# Wifi-Bluetooth-Power.net
KiCad netlist of a schematic drawn in Altium Designer
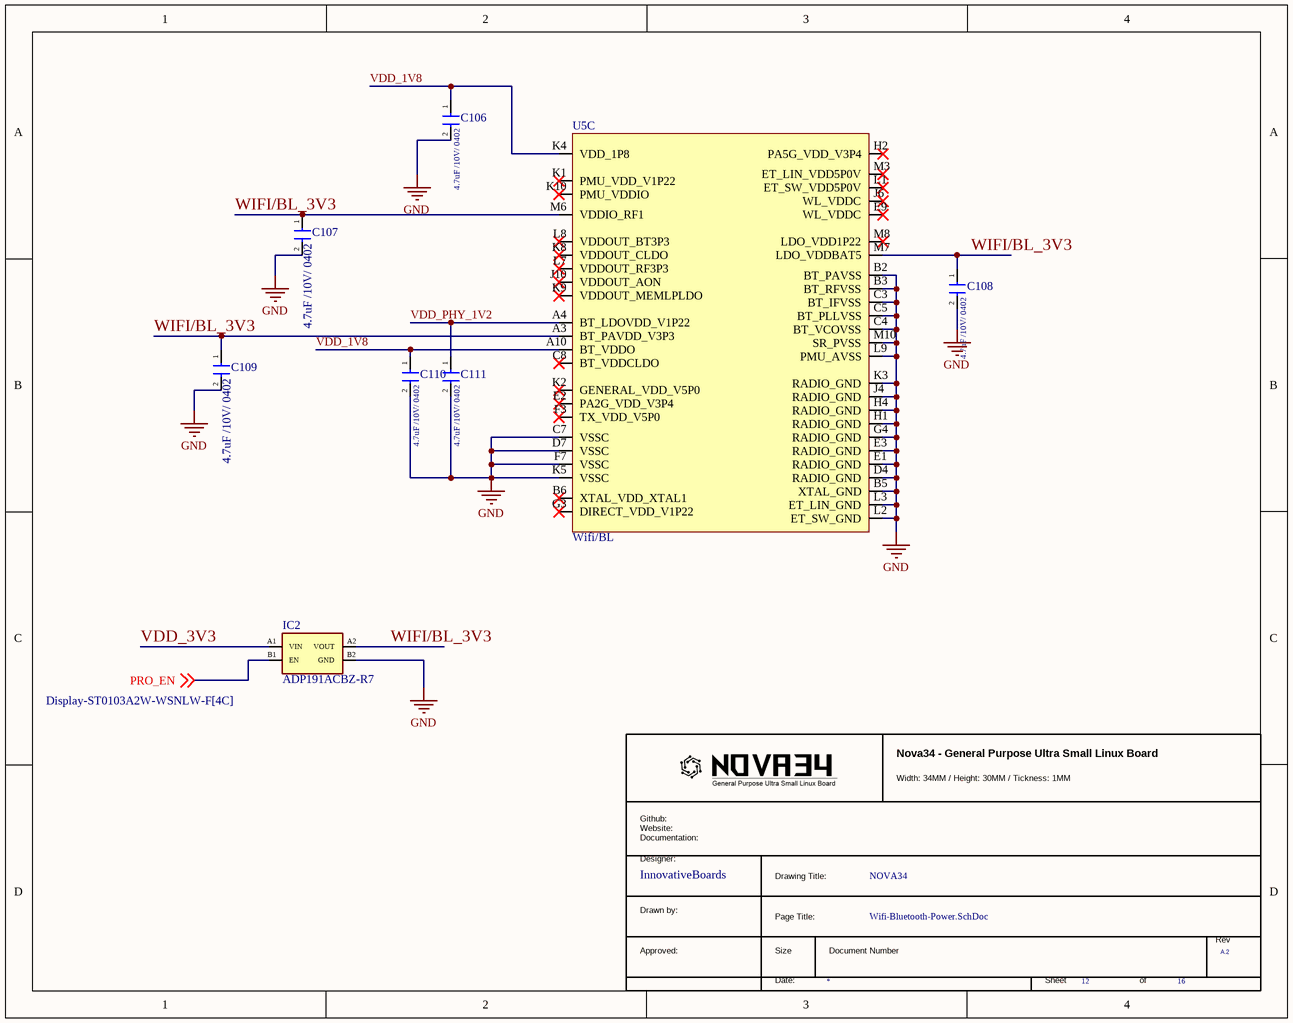
[diagram p0: Wifi-Bluetooth-Power.SchDoc]

(export (version "E")
  (design (tool "Eeschema 10.0.6"))
  (components
    (comp (ref "*")
      (value "TitleBlock_MCPG")
      (fields (field (name "REVCODE") "A.2"))
      (libsource (lib "Nova_SCHLIB") (part "TitleBlock_MCPG"))
    )
    (comp (ref "C106")
      (value "4.7uF /10V/ 0402")
      (footprint "CAPC1005X70N")
      (description "Multilayer Ceramic Capacitors MLCC - SMD/SMT 0402 X6S 4.7 F 20 10VDC AEC-Q200")
      (fields
        (field (name "MANUFACTURER_PART_NUMBER") "GRT155C81A475ME13J")
        (field (name "MOUSER PART NUMBER") "81-GRT155C81A475ME3J")
      )
      (libsource (lib "Nova_SCHLIB") (part "GRT155C81A475ME13J"))
    )
    (comp (ref "C107")
      (value "4.7uF /10V/ 0402")
      (footprint "CAPC1005X70N")
      (description "Multilayer Ceramic Capacitors MLCC - SMD/SMT 0402 X6S 4.7 F 20 10VDC AEC-Q200")
      (fields
        (field (name "MANUFACTURER_PART_NUMBER") "GRT155C81A475ME13J")
        (field (name "MOUSER PART NUMBER") "81-GRT155C81A475ME3J")
      )
      (libsource (lib "Nova_SCHLIB") (part "GRT155C81A475ME13J"))
    )
    (comp (ref "C108")
      (value "4.7uF /10V/ 0402")
      (footprint "CAPC1005X70N")
      (description "Multilayer Ceramic Capacitors MLCC - SMD/SMT 0402 X6S 4.7 F 20 10VDC AEC-Q200")
      (fields
        (field (name "MANUFACTURER_PART_NUMBER") "GRT155C81A475ME13J")
        (field (name "MOUSER PART NUMBER") "81-GRT155C81A475ME3J")
      )
      (libsource (lib "Nova_SCHLIB") (part "GRT155C81A475ME13J"))
    )
    (comp (ref "C109")
      (value "4.7uF /10V/ 0402")
      (footprint "CAPC1005X70N")
      (description "Multilayer Ceramic Capacitors MLCC - SMD/SMT 0402 X6S 4.7 F 20 10VDC AEC-Q200")
      (fields
        (field (name "MANUFACTURER_PART_NUMBER") "GRT155C81A475ME13J")
        (field (name "MOUSER PART NUMBER") "81-GRT155C81A475ME3J")
      )
      (libsource (lib "Nova_SCHLIB") (part "GRT155C81A475ME13J"))
    )
    (comp (ref "C110")
      (value "4.7uF /10V/ 0402")
      (footprint "CAPC1005X70N")
      (description "Multilayer Ceramic Capacitors MLCC - SMD/SMT 0402 X6S 4.7 F 20 10VDC AEC-Q200")
      (fields
        (field (name "MANUFACTURER_PART_NUMBER") "GRT155C81A475ME13J")
        (field (name "MOUSER PART NUMBER") "81-GRT155C81A475ME3J")
      )
      (libsource (lib "Nova_SCHLIB") (part "GRT155C81A475ME13J"))
    )
    (comp (ref "C111")
      (value "4.7uF /10V/ 0402")
      (footprint "CAPC1005X70N")
      (description "Multilayer Ceramic Capacitors MLCC - SMD/SMT 0402 X6S 4.7 F 20 10VDC AEC-Q200")
      (fields
        (field (name "MANUFACTURER_PART_NUMBER") "GRT155C81A475ME13J")
        (field (name "MOUSER PART NUMBER") "81-GRT155C81A475ME3J")
      )
      (libsource (lib "Nova_SCHLIB") (part "GRT155C81A475ME13J"))
    )
    (comp (ref "IC2")
      (value "ADP191ACBZ-R7")
      (footprint "BGA4C40P2X2_76X76X66")
      (description "Integrated Circuit")
      (fields (field (name "MOUSER PART NUMBER") "584-ADP191ACBZ-R7"))
      (libsource (lib "Nova_SCHLIB") (part "ADP191ACBZ-R7"))
    )
    (comp (ref "U5")
      (value "Wifi/BL")
      (footprint "106 BALL WLBGA 3.76X4.43X0.53 MM")
      (libsource (lib "Nova_SCHLIB") (part "CYW43012"))
    )
  )
  (nets
    (net (code "1") (name "/VDD_1V8") (class "Default")
      (node (ref "C106") (pin "1") (pinfunction "1_1") (pintype "passive"))
      (node (ref "C110") (pin "1") (pinfunction "1_1") (pintype "passive"))
      (node (ref "U5") (pin "A10") (pinfunction "BT_VDDO_A10") (pintype "passive"))
      (node (ref "U5") (pin "K4") (pinfunction "VDD_1P8_K4") (pintype "passive"))
    )
    (net (code "2") (name "/VDD_3V3") (class "Default")
      (node (ref "IC2") (pin "A1") (pinfunction "VIN_A1") (pintype "passive"))
    )
    (net (code "3") (name "/VDD_PHY_1V2") (class "Default")
      (node (ref "C111") (pin "1") (pinfunction "1_1") (pintype "passive"))
      (node (ref "U5") (pin "A4") (pinfunction "BT_LDOVDD_V1P22_A4") (pintype "passive"))
    )
    (net (code "4") (name "/WIFI{slash}BL_3V3") (class "Default")
      (node (ref "C107") (pin "1") (pinfunction "1_1") (pintype "passive"))
      (node (ref "C108") (pin "1") (pinfunction "1_1") (pintype "passive"))
      (node (ref "C109") (pin "1") (pinfunction "1_1") (pintype "passive"))
      (node (ref "IC2") (pin "A2") (pinfunction "VOUT_A2") (pintype "passive"))
      (node (ref "U5") (pin "A3") (pinfunction "BT_PAVDD_V3P3_A3") (pintype "passive"))
      (node (ref "U5") (pin "M6") (pinfunction "VDDIO_RF1_M6") (pintype "passive"))
      (node (ref "U5") (pin "M7") (pinfunction "LDO_VDDBAT5_M7") (pintype "passive"))
    )
    (net (code "5") (name "GND") (class "Default")
      (node (ref "C106") (pin "2") (pinfunction "2_2") (pintype "passive"))
      (node (ref "C107") (pin "2") (pinfunction "2_2") (pintype "passive"))
      (node (ref "C108") (pin "2") (pinfunction "2_2") (pintype "passive"))
      (node (ref "C109") (pin "2") (pinfunction "2_2") (pintype "passive"))
      (node (ref "C110") (pin "2") (pinfunction "2_2") (pintype "passive"))
      (node (ref "C111") (pin "2") (pinfunction "2_2") (pintype "passive"))
      (node (ref "IC2") (pin "B2") (pinfunction "GND_B2") (pintype "passive"))
      (node (ref "U5") (pin "B2") (pinfunction "BT_PAVSS_B2") (pintype "passive"))
      (node (ref "U5") (pin "B3") (pinfunction "BT_RFVSS_B3") (pintype "passive"))
      (node (ref "U5") (pin "B5") (pinfunction "XTAL_GND_B5") (pintype "passive"))
      (node (ref "U5") (pin "C3") (pinfunction "BT_IFVSS_C3") (pintype "passive"))
      (node (ref "U5") (pin "C4") (pinfunction "BT_VCOVSS_C4") (pintype "passive"))
      (node (ref "U5") (pin "C5") (pinfunction "BT_PLLVSS_C5") (pintype "passive"))
      (node (ref "U5") (pin "C7") (pinfunction "VSSC_C7") (pintype "passive"))
      (node (ref "U5") (pin "D4") (pinfunction "RADIO_GND_D4") (pintype "passive"))
      (node (ref "U5") (pin "D7") (pinfunction "VSSC_D7") (pintype "passive"))
      (node (ref "U5") (pin "E1") (pinfunction "RADIO_GND_E1") (pintype "passive"))
      (node (ref "U5") (pin "E3") (pinfunction "RADIO_GND_E3") (pintype "passive"))
      (node (ref "U5") (pin "F7") (pinfunction "VSSC_F7") (pintype "passive"))
      (node (ref "U5") (pin "G4") (pinfunction "RADIO_GND_G4") (pintype "passive"))
      (node (ref "U5") (pin "H1") (pinfunction "RADIO_GND_H1") (pintype "passive"))
      (node (ref "U5") (pin "H4") (pinfunction "RADIO_GND_H4") (pintype "passive"))
      (node (ref "U5") (pin "J4") (pinfunction "RADIO_GND_J4") (pintype "passive"))
      (node (ref "U5") (pin "K3") (pinfunction "RADIO_GND_K3") (pintype "passive"))
      (node (ref "U5") (pin "K5") (pinfunction "VSSC_K5") (pintype "passive"))
      (node (ref "U5") (pin "L2") (pinfunction "ET_SW_GND_L2") (pintype "passive"))
      (node (ref "U5") (pin "L3") (pinfunction "ET_LIN_GND_L3") (pintype "passive"))
      (node (ref "U5") (pin "L9") (pinfunction "PMU_AVSS_L9") (pintype "passive"))
      (node (ref "U5") (pin "M10") (pinfunction "SR_PVSS_M10") (pintype "passive"))
    )
    (net (code "6") (name "PRO_EN") (class "Default")
      (node (ref "IC2") (pin "B1") (pinfunction "EN_B1") (pintype "passive"))
    )
    (net (code "7") (name "unconnected-(U5C-BT_VDDCLDO-PadC8)") (class "Default")
      (node (ref "U5") (pin "C8") (pinfunction "BT_VDDCLDO_C8") (pintype "passive+no_connect"))
    )
    (net (code "8") (name "unconnected-(U5C-DIRECT_VDD_V1P22-PadG3)") (class "Default")
      (node (ref "U5") (pin "G3") (pinfunction "DIRECT_VDD_V1P22_G3") (pintype "passive+no_connect"))
    )
    (net (code "9") (name "unconnected-(U5C-ET_LIN_VDD5P0V-PadM3)") (class "Default")
      (node (ref "U5") (pin "M3") (pinfunction "ET_LIN_VDD5P0V_M3") (pintype "passive+no_connect"))
    )
    (net (code "10") (name "unconnected-(U5C-ET_SW_VDD5P0V-PadL1)") (class "Default")
      (node (ref "U5") (pin "L1") (pinfunction "ET_SW_VDD5P0V_L1") (pintype "passive+no_connect"))
    )
    (net (code "11") (name "unconnected-(U5C-GENERAL_VDD_V5P0-PadK2)") (class "Default")
      (node (ref "U5") (pin "K2") (pinfunction "GENERAL_VDD_V5P0_K2") (pintype "passive+no_connect"))
    )
    (net (code "12") (name "unconnected-(U5C-LDO_VDD1P22-PadM8)") (class "Default")
      (node (ref "U5") (pin "M8") (pinfunction "LDO_VDD1P22_M8") (pintype "passive+no_connect"))
    )
    (net (code "13") (name "unconnected-(U5C-PA2G_VDD_V3P4-PadE2)") (class "Default")
      (node (ref "U5") (pin "E2") (pinfunction "PA2G_VDD_V3P4_E2") (pintype "passive+no_connect"))
    )
    (net (code "14") (name "unconnected-(U5C-PA5G_VDD_V3P4-PadH2)") (class "Default")
      (node (ref "U5") (pin "H2") (pinfunction "PA5G_VDD_V3P4_H2") (pintype "passive+no_connect"))
    )
    (net (code "15") (name "unconnected-(U5C-PMU_VDDIO-PadK10)") (class "Default")
      (node (ref "U5") (pin "K10") (pinfunction "PMU_VDDIO_K10") (pintype "passive+no_connect"))
    )
    (net (code "16") (name "unconnected-(U5C-PMU_VDD_V1P22-PadK1)") (class "Default")
      (node (ref "U5") (pin "K1") (pinfunction "PMU_VDD_V1P22_K1") (pintype "passive+no_connect"))
    )
    (net (code "17") (name "unconnected-(U5C-TX_VDD_V5P0-PadF3)") (class "Default")
      (node (ref "U5") (pin "F3") (pinfunction "TX_VDD_V5P0_F3") (pintype "passive+no_connect"))
    )
    (net (code "18") (name "unconnected-(U5C-VDDOUT_AON-PadJ10)") (class "Default")
      (node (ref "U5") (pin "J10") (pinfunction "VDDOUT_AON_J10") (pintype "passive+no_connect"))
    )
    (net (code "19") (name "unconnected-(U5C-VDDOUT_BT3P3-PadL8)") (class "Default")
      (node (ref "U5") (pin "L8") (pinfunction "VDDOUT_BT3P3_L8") (pintype "passive+no_connect"))
    )
    (net (code "20") (name "unconnected-(U5C-VDDOUT_CLDO-PadK8)") (class "Default")
      (node (ref "U5") (pin "K8") (pinfunction "VDDOUT_CLDO_K8") (pintype "passive+no_connect"))
    )
    (net (code "21") (name "unconnected-(U5C-VDDOUT_MEMLPLDO-PadK9)") (class "Default")
      (node (ref "U5") (pin "K9") (pinfunction "VDDOUT_MEMLPLDO_K9") (pintype "passive+no_connect"))
    )
    (net (code "22") (name "unconnected-(U5C-VDDOUT_RF3P3-PadL7)") (class "Default")
      (node (ref "U5") (pin "L7") (pinfunction "VDDOUT_RF3P3_L7") (pintype "passive+no_connect"))
    )
    (net (code "23") (name "unconnected-(U5C-WL_VDDC-PadE9)") (class "Default")
      (node (ref "U5") (pin "E9") (pinfunction "WL_VDDC_E9") (pintype "passive+no_connect"))
    )
    (net (code "24") (name "unconnected-(U5C-WL_VDDC-PadJ6)") (class "Default")
      (node (ref "U5") (pin "J6") (pinfunction "WL_VDDC_J6") (pintype "passive+no_connect"))
    )
    (net (code "25") (name "unconnected-(U5C-XTAL_VDD_XTAL1-PadB6)") (class "Default")
      (node (ref "U5") (pin "B6") (pinfunction "XTAL_VDD_XTAL1_B6") (pintype "passive+no_connect"))
    )
  )
)
